# placa_nano.net
KiCad netlist of a schematic drawn in EAGLE
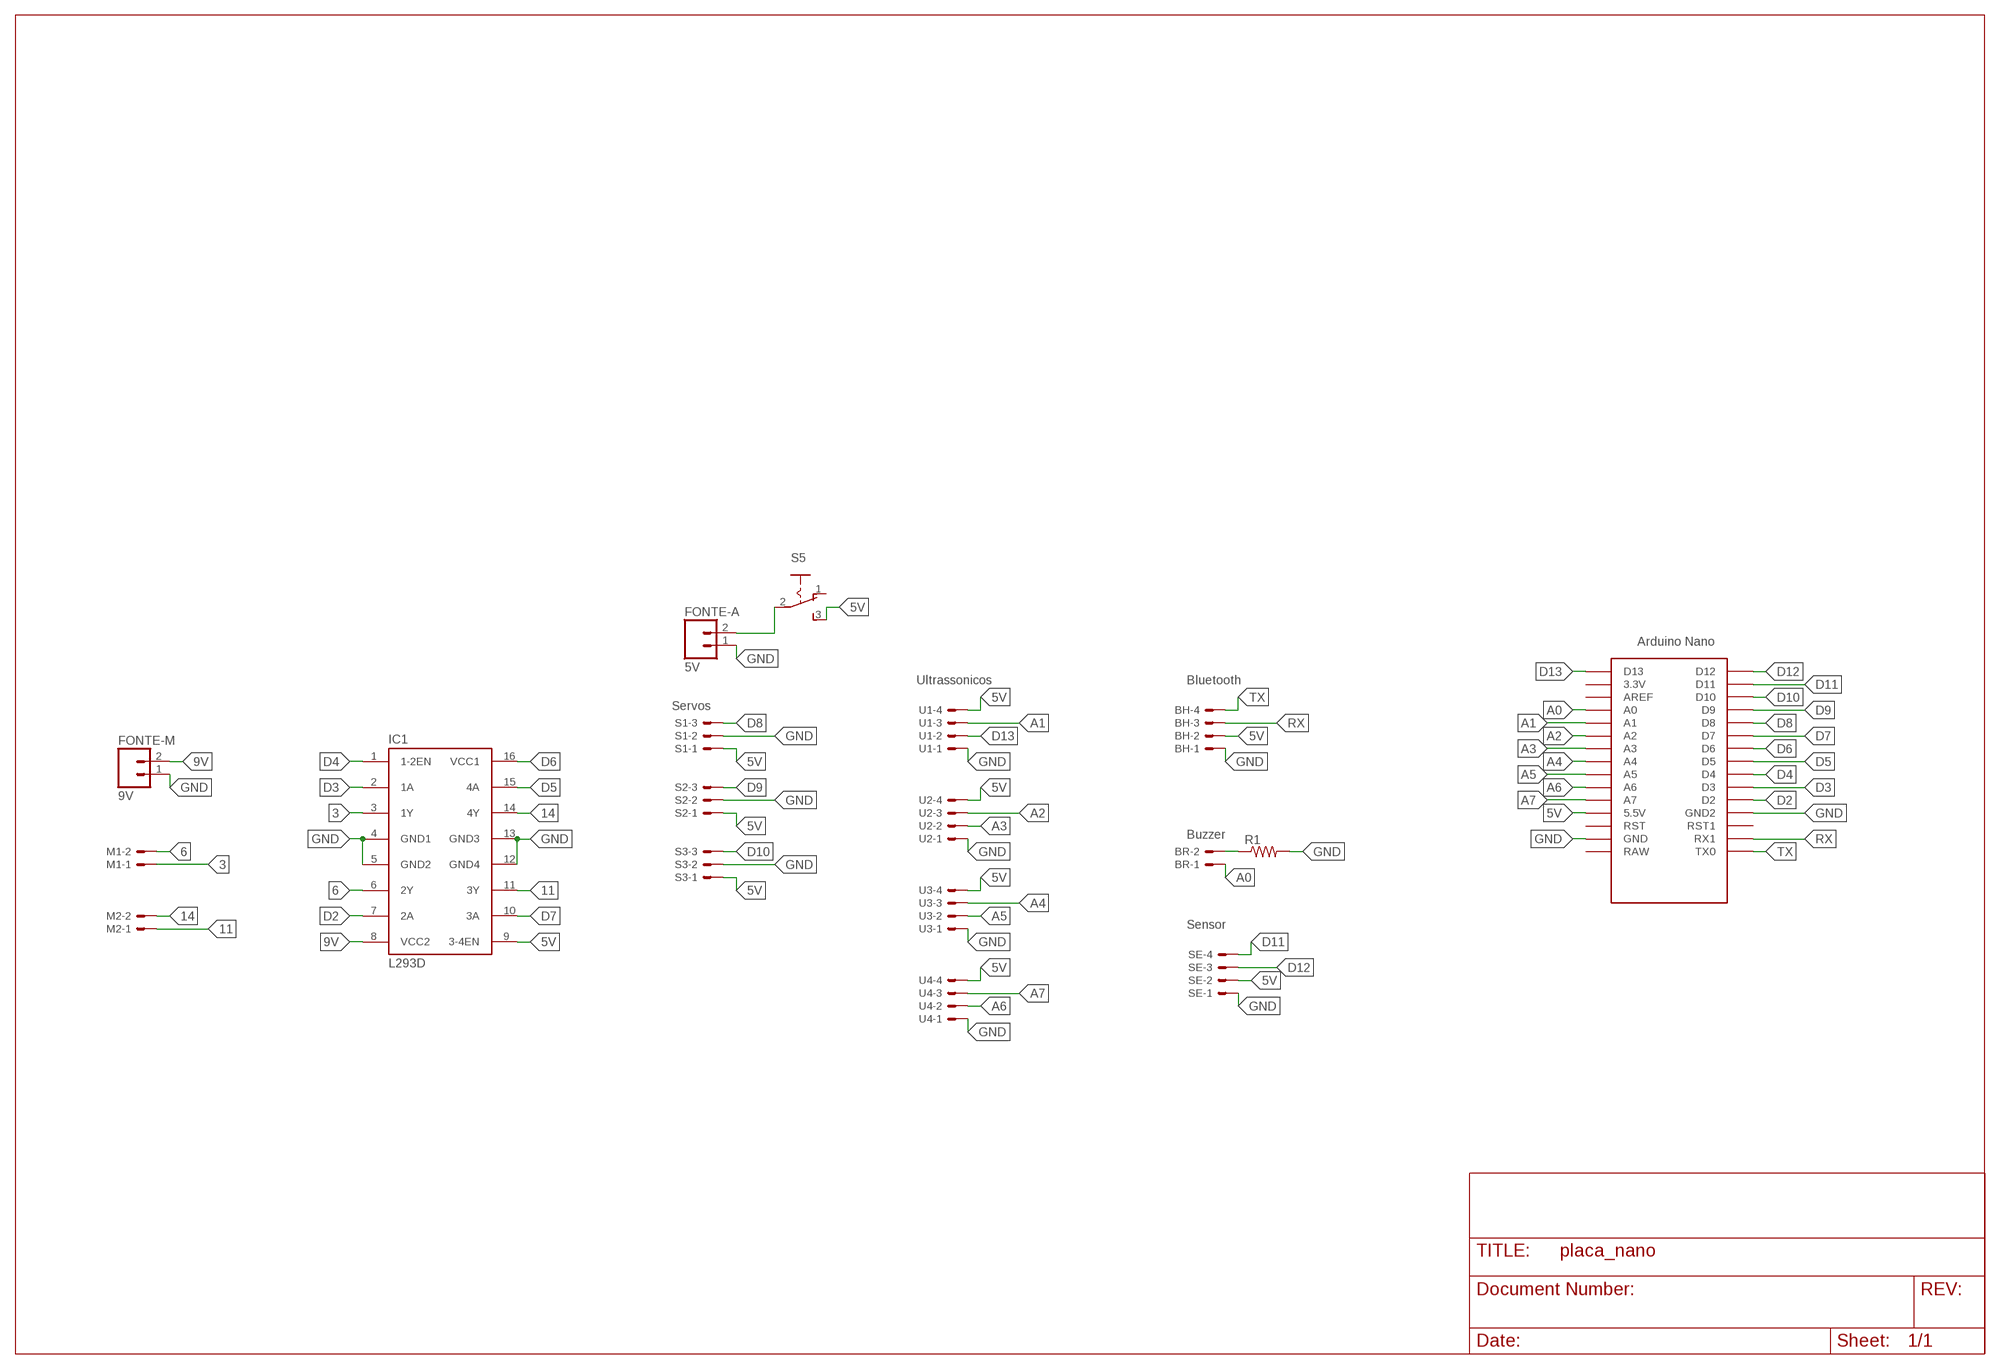
[diagram p0: schematic, sheet 1]

(export (version "E")
  (design (tool "Eeschema 10.0.6"))
  (components
    (comp (ref "BH")
      (value "22-23-2041")
      (footprint "eagle-import:22-23-2041")
      (fields (field (name "MF") "MOLEX"))
      (libsource (lib "eagle-import") (part "22-23-2041"))
    )
    (comp (ref "BR")
      (value "22-23-2021")
      (footprint "eagle-import:22-23-2021")
      (fields (field (name "MF") "MOLEX"))
      (libsource (lib "eagle-import") (part "22-23-2021"))
    )
    (comp (ref "FONTE-A")
      (value "5V")
      (footprint "eagle-import:02P")
      (libsource (lib "eagle-import") (part "M02"))
    )
    (comp (ref "FONTE-M")
      (value "9V")
      (footprint "eagle-import:02P")
      (libsource (lib "eagle-import") (part "M02"))
    )
    (comp (ref "IC1")
      (value "L293D")
      (footprint "eagle-import:DIL16")
      (libsource (lib "eagle-import") (part "L293D"))
    )
    (comp (ref "M1")
      (value "22-23-2021")
      (footprint "eagle-import:22-23-2021")
      (fields (field (name "MF") "MOLEX"))
      (libsource (lib "eagle-import") (part "22-23-2021"))
    )
    (comp (ref "M2")
      (value "22-23-2021")
      (footprint "eagle-import:22-23-2021")
      (fields (field (name "MF") "MOLEX"))
      (libsource (lib "eagle-import") (part "22-23-2021"))
    )
    (comp (ref "R1")
      (value "R-US_0207/10")
      (footprint "eagle-import:0207_10")
      (libsource (lib "eagle-import") (part "R-US_0207/10"))
    )
    (comp (ref "S1")
      (value "22-23-2031")
      (footprint "eagle-import:22-23-2031")
      (fields (field (name "MF") "MOLEX"))
      (libsource (lib "eagle-import") (part "22-23-2031"))
    )
    (comp (ref "S2")
      (value "22-23-2031")
      (footprint "eagle-import:22-23-2031")
      (fields (field (name "MF") "MOLEX"))
      (libsource (lib "eagle-import") (part "22-23-2031"))
    )
    (comp (ref "S3")
      (value "22-23-2031")
      (footprint "eagle-import:22-23-2031")
      (fields (field (name "MF") "MOLEX"))
      (libsource (lib "eagle-import") (part "22-23-2031"))
    )
    (comp (ref "S5")
      (value "255SB")
      (footprint "eagle-import:255SB")
      (libsource (lib "eagle-import") (part "255SB"))
    )
    (comp (ref "SE")
      (value "22-23-2041")
      (footprint "eagle-import:22-23-2041")
      (fields (field (name "MF") "MOLEX"))
      (libsource (lib "eagle-import") (part "22-23-2041"))
    )
    (comp (ref "U$1")
      (value "NANO")
      (footprint "eagle-import:NANO")
      (libsource (lib "eagle-import") (part "NANO"))
    )
    (comp (ref "U1")
      (value "22-23-2041")
      (footprint "eagle-import:22-23-2041")
      (fields (field (name "MF") "MOLEX"))
      (libsource (lib "eagle-import") (part "22-23-2041"))
    )
    (comp (ref "U2")
      (value "22-23-2041")
      (footprint "eagle-import:22-23-2041")
      (fields (field (name "MF") "MOLEX"))
      (libsource (lib "eagle-import") (part "22-23-2041"))
    )
    (comp (ref "U3")
      (value "22-23-2041")
      (footprint "eagle-import:22-23-2041")
      (fields (field (name "MF") "MOLEX"))
      (libsource (lib "eagle-import") (part "22-23-2041"))
    )
    (comp (ref "U4")
      (value "22-23-2041")
      (footprint "eagle-import:22-23-2041")
      (fields (field (name "MF") "MOLEX"))
      (libsource (lib "eagle-import") (part "22-23-2041"))
    )
  )
  (nets
    (net (code "1") (name "3") (class "Default")
      (node (ref "IC1") (pin "3") (pinfunction "1Y_3") (pintype "output"))
      (node (ref "M1") (pin "1") (pinfunction "S_1") (pintype "passive"))
    )
    (net (code "2") (name "5V") (class "Default")
      (node (ref "BH") (pin "2") (pinfunction "S_2") (pintype "passive"))
      (node (ref "FONTE-A") (pin "2") (pinfunction "2_2") (pintype "passive"))
      (node (ref "IC1") (pin "9") (pinfunction "3-4EN_9") (pintype "input"))
      (node (ref "S1") (pin "1") (pinfunction "S_1") (pintype "passive"))
      (node (ref "S2") (pin "1") (pinfunction "S_1") (pintype "passive"))
      (node (ref "S3") (pin "1") (pinfunction "S_1") (pintype "passive"))
      (node (ref "S5") (pin "2") (pinfunction "P_2") (pintype "passive"))
      (node (ref "S5") (pin "3") (pinfunction "S_3") (pintype "passive"))
      (node (ref "SE") (pin "2") (pinfunction "S_2") (pintype "passive"))
      (node (ref "U$1") (pin "5V") (pinfunction "5.5V_5V") (pintype "bidirectional"))
      (node (ref "U1") (pin "4") (pinfunction "S_4") (pintype "passive"))
      (node (ref "U2") (pin "4") (pinfunction "S_4") (pintype "passive"))
      (node (ref "U3") (pin "4") (pinfunction "S_4") (pintype "passive"))
      (node (ref "U4") (pin "4") (pinfunction "S_4") (pintype "passive"))
    )
    (net (code "3") (name "6") (class "Default")
      (node (ref "IC1") (pin "6") (pinfunction "2Y_6") (pintype "output"))
      (node (ref "M1") (pin "2") (pinfunction "S_2") (pintype "passive"))
    )
    (net (code "4") (name "9V") (class "Default")
      (node (ref "FONTE-M") (pin "2") (pinfunction "2_2") (pintype "passive"))
      (node (ref "IC1") (pin "8") (pinfunction "VCC2_8") (pintype "power_in"))
    )
    (net (code "5") (name "11") (class "Default")
      (node (ref "IC1") (pin "11") (pinfunction "3Y_11") (pintype "output"))
      (node (ref "M2") (pin "1") (pinfunction "S_1") (pintype "passive"))
    )
    (net (code "6") (name "14") (class "Default")
      (node (ref "IC1") (pin "14") (pinfunction "4Y_14") (pintype "output"))
      (node (ref "M2") (pin "2") (pinfunction "S_2") (pintype "passive"))
    )
    (net (code "7") (name "A0") (class "Default")
      (node (ref "BR") (pin "1") (pinfunction "S_1") (pintype "passive"))
      (node (ref "U$1") (pin "A0") (pinfunction "A0_A0") (pintype "bidirectional"))
    )
    (net (code "8") (name "A1") (class "Default")
      (node (ref "U$1") (pin "A1") (pinfunction "A1_A1") (pintype "bidirectional"))
      (node (ref "U1") (pin "3") (pinfunction "S_3") (pintype "passive"))
    )
    (net (code "9") (name "A2") (class "Default")
      (node (ref "U$1") (pin "A2") (pinfunction "A2_A2") (pintype "bidirectional"))
      (node (ref "U2") (pin "3") (pinfunction "S_3") (pintype "passive"))
    )
    (net (code "10") (name "A3") (class "Default")
      (node (ref "U$1") (pin "A3") (pinfunction "A3_A3") (pintype "bidirectional"))
      (node (ref "U2") (pin "2") (pinfunction "S_2") (pintype "passive"))
    )
    (net (code "11") (name "A4") (class "Default")
      (node (ref "U$1") (pin "A4") (pinfunction "A4_A4") (pintype "bidirectional"))
      (node (ref "U3") (pin "3") (pinfunction "S_3") (pintype "passive"))
    )
    (net (code "12") (name "A5") (class "Default")
      (node (ref "U$1") (pin "A5") (pinfunction "A5_A5") (pintype "bidirectional"))
      (node (ref "U3") (pin "2") (pinfunction "S_2") (pintype "passive"))
    )
    (net (code "13") (name "A6") (class "Default")
      (node (ref "U$1") (pin "A6") (pinfunction "A6_A6") (pintype "bidirectional"))
      (node (ref "U4") (pin "2") (pinfunction "S_2") (pintype "passive"))
    )
    (net (code "14") (name "A7") (class "Default")
      (node (ref "U$1") (pin "A7") (pinfunction "A7_A7") (pintype "bidirectional"))
      (node (ref "U4") (pin "3") (pinfunction "S_3") (pintype "passive"))
    )
    (net (code "15") (name "D2") (class "Default")
      (node (ref "IC1") (pin "7") (pinfunction "2A_7") (pintype "input"))
      (node (ref "U$1") (pin "D2") (pinfunction "D2_D2") (pintype "bidirectional"))
    )
    (net (code "16") (name "D3") (class "Default")
      (node (ref "IC1") (pin "2") (pinfunction "1A_2") (pintype "input"))
      (node (ref "U$1") (pin "D3") (pinfunction "D3_D3") (pintype "bidirectional"))
    )
    (net (code "17") (name "D4") (class "Default")
      (node (ref "IC1") (pin "1") (pinfunction "1-2EN_1") (pintype "input"))
      (node (ref "U$1") (pin "D4") (pinfunction "D4_D4") (pintype "bidirectional"))
    )
    (net (code "18") (name "D5") (class "Default")
      (node (ref "IC1") (pin "15") (pinfunction "4A_15") (pintype "input"))
      (node (ref "U$1") (pin "D5") (pinfunction "D5_D5") (pintype "bidirectional"))
    )
    (net (code "19") (name "D6") (class "Default")
      (node (ref "IC1") (pin "16") (pinfunction "VCC1_16") (pintype "power_in"))
      (node (ref "U$1") (pin "D6") (pinfunction "D6_D6") (pintype "bidirectional"))
    )
    (net (code "20") (name "D7") (class "Default")
      (node (ref "IC1") (pin "10") (pinfunction "3A_10") (pintype "input"))
      (node (ref "U$1") (pin "D7") (pinfunction "D7_D7") (pintype "bidirectional"))
    )
    (net (code "21") (name "D8") (class "Default")
      (node (ref "S1") (pin "3") (pinfunction "S_3") (pintype "passive"))
      (node (ref "U$1") (pin "D8") (pinfunction "D8_D8") (pintype "bidirectional"))
    )
    (net (code "22") (name "D9") (class "Default")
      (node (ref "S2") (pin "3") (pinfunction "S_3") (pintype "passive"))
      (node (ref "U$1") (pin "D9") (pinfunction "D9_D9") (pintype "bidirectional"))
    )
    (net (code "23") (name "D10") (class "Default")
      (node (ref "S3") (pin "3") (pinfunction "S_3") (pintype "passive"))
      (node (ref "U$1") (pin "D10") (pinfunction "D10_D10") (pintype "bidirectional"))
    )
    (net (code "24") (name "D11") (class "Default")
      (node (ref "SE") (pin "4") (pinfunction "S_4") (pintype "passive"))
      (node (ref "U$1") (pin "D11") (pinfunction "D11_D11") (pintype "bidirectional"))
    )
    (net (code "25") (name "D12") (class "Default")
      (node (ref "SE") (pin "3") (pinfunction "S_3") (pintype "passive"))
      (node (ref "U$1") (pin "D12") (pinfunction "D12_D12") (pintype "bidirectional"))
    )
    (net (code "26") (name "D13") (class "Default")
      (node (ref "U$1") (pin "D13") (pinfunction "D13_D13") (pintype "bidirectional"))
      (node (ref "U1") (pin "2") (pinfunction "S_2") (pintype "passive"))
    )
    (net (code "27") (name "GND") (class "Default")
      (node (ref "BH") (pin "1") (pinfunction "S_1") (pintype "passive"))
      (node (ref "FONTE-A") (pin "1") (pinfunction "1_1") (pintype "passive"))
      (node (ref "FONTE-M") (pin "1") (pinfunction "1_1") (pintype "passive"))
      (node (ref "IC1") (pin "12") (pinfunction "GND4_12") (pintype "power_in"))
      (node (ref "IC1") (pin "13") (pinfunction "GND3_13") (pintype "power_in"))
      (node (ref "IC1") (pin "4") (pinfunction "GND1_4") (pintype "power_in"))
      (node (ref "IC1") (pin "5") (pinfunction "GND2_5") (pintype "power_in"))
      (node (ref "R1") (pin "2") (pinfunction "2_2") (pintype "passive"))
      (node (ref "S1") (pin "2") (pinfunction "S_2") (pintype "passive"))
      (node (ref "S2") (pin "2") (pinfunction "S_2") (pintype "passive"))
      (node (ref "S3") (pin "2") (pinfunction "S_2") (pintype "passive"))
      (node (ref "SE") (pin "1") (pinfunction "S_1") (pintype "passive"))
      (node (ref "U$1") (pin "GND") (pinfunction "GND_GND") (pintype "bidirectional"))
      (node (ref "U$1") (pin "GND1") (pinfunction "GND2_GND1") (pintype "bidirectional"))
      (node (ref "U1") (pin "1") (pinfunction "S_1") (pintype "passive"))
      (node (ref "U2") (pin "1") (pinfunction "S_1") (pintype "passive"))
      (node (ref "U3") (pin "1") (pinfunction "S_1") (pintype "passive"))
      (node (ref "U4") (pin "1") (pinfunction "S_1") (pintype "passive"))
    )
    (net (code "28") (name "Net-(BRB-S)") (class "Default")
      (node (ref "BR") (pin "2") (pinfunction "S_2") (pintype "passive"))
      (node (ref "R1") (pin "1") (pinfunction "1_1") (pintype "passive"))
    )
    (net (code "29") (name "RX") (class "Default")
      (node (ref "BH") (pin "3") (pinfunction "S_3") (pintype "passive"))
      (node (ref "U$1") (pin "RX1") (pinfunction "RX1_RX1") (pintype "bidirectional"))
    )
    (net (code "30") (name "TX") (class "Default")
      (node (ref "BH") (pin "4") (pinfunction "S_4") (pintype "passive"))
      (node (ref "U$1") (pin "TX0") (pinfunction "TX0_TX0") (pintype "bidirectional"))
    )
    (net (code "31") (name "unconnected-(S5-O-Pad1)") (class "Default")
      (node (ref "S5") (pin "1") (pinfunction "O_1") (pintype "passive"))
    )
    (net (code "32") (name "unconnected-(U$1-Pad3.3V)") (class "Default")
      (node (ref "U$1") (pin "3.3V") (pinfunction "3.3V_3.3V") (pintype "bidirectional"))
    )
    (net (code "33") (name "unconnected-(U$1-PadAREF)") (class "Default")
      (node (ref "U$1") (pin "AREF") (pinfunction "AREF_AREF") (pintype "bidirectional"))
    )
    (net (code "34") (name "unconnected-(U$1-PadRAW)") (class "Default")
      (node (ref "U$1") (pin "RAW") (pinfunction "RAW_RAW") (pintype "bidirectional"))
    )
    (net (code "35") (name "unconnected-(U$1-PadRST)") (class "Default")
      (node (ref "U$1") (pin "RST") (pinfunction "RST_RST") (pintype "bidirectional"))
    )
    (net (code "36") (name "unconnected-(U$1-PadRST1)") (class "Default")
      (node (ref "U$1") (pin "RST1") (pinfunction "RST1_RST1") (pintype "bidirectional"))
    )
  )
)
